# 5V-buck.net
KiCad netlist of a schematic drawn in Altium Designer
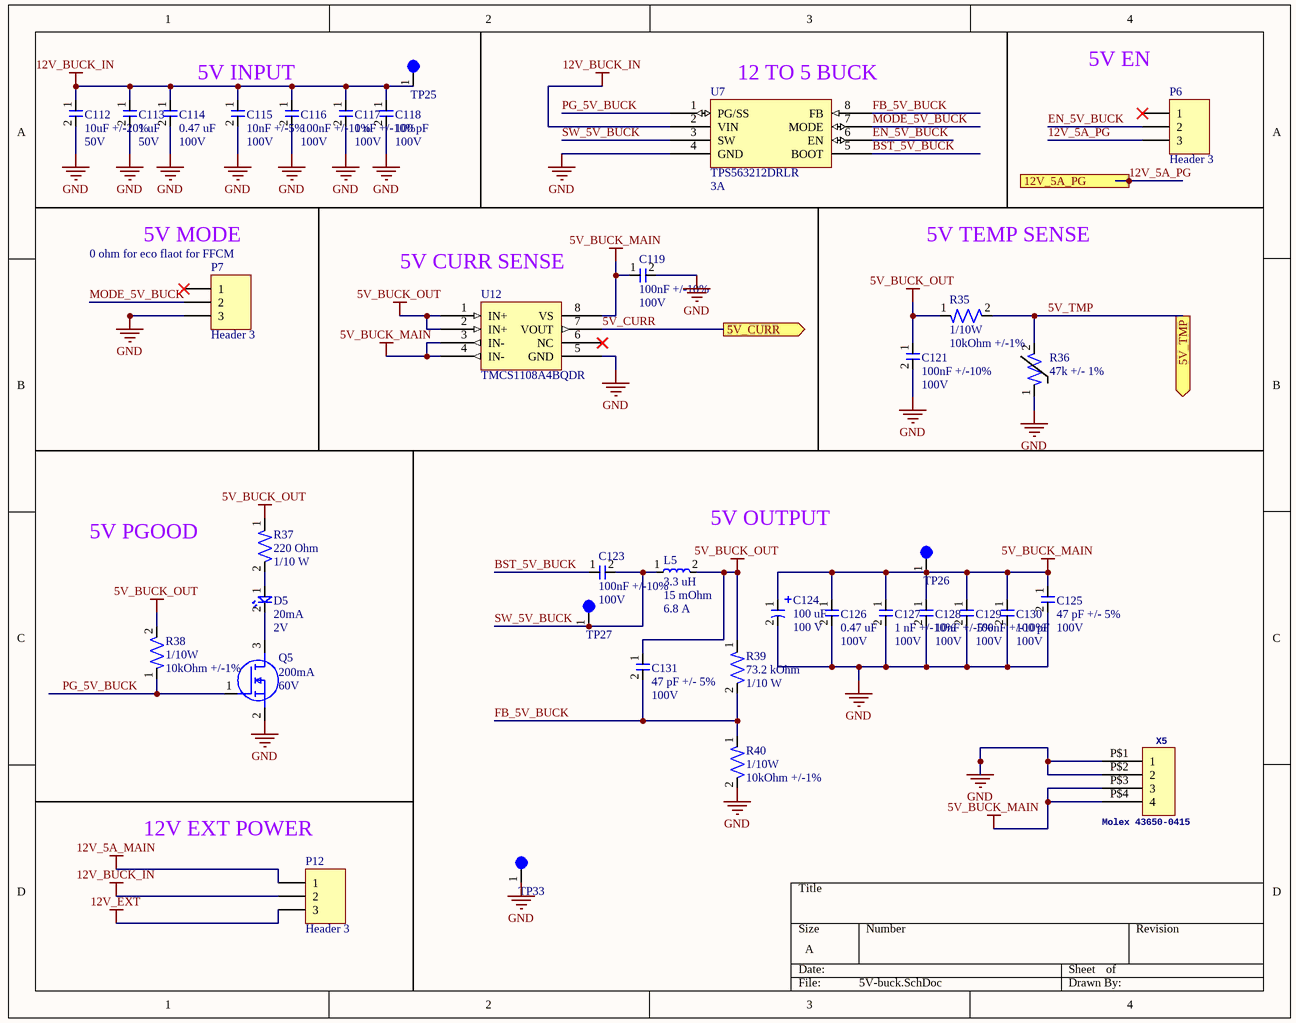
[diagram p0: 5V-buck.SchDoc]

(export (version "E")
  (design (tool "Eeschema 10.0.6"))
  (components
    (comp (ref "C112")
      (value "CL31B106KBHNNNE")
      (footprint "CAP-1206")
      (description "10 µF ±10% 50V Ceramic Capacitor X7R 1206 (3216 Metric)")
      (fields
        (field (name "MANUFACTURER") "Samsung Electro-Mechanics")
        (field (name "CAPACITANCE") "10uF +/-20%")
        (field (name "VOLTAGE RATING") "50V")
      )
      (libsource (lib "MasterLib") (part "CAP-10U-0001"))
    )
    (comp (ref "C113")
      (value "UMK107AB7105KA-T")
      (footprint "CAP-0603")
      (description "1 µF ±10% 50V Ceramic Capacitor X7R 0603 (1608 Metric)")
      (fields (field (name "CAPACITANCE") "1 uF") (field (name "VOLTAGE") "50V"))
      (libsource (lib "MasterLib") (part "CAP-1U-0002"))
    )
    (comp (ref "C114")
      (value "KAM21KR72A474KL")
      (footprint "CAP-0805")
      (description "0.47 µF ±10% 100V Ceramic Capacitor X7R 0805 (2012 Metric)")
      (fields
        (field (name "TOLERANCE") "+/- 10%")
        (field (name "CAPACITANCE") "0.47 uF")
        (field (name "VOLTAGE") "100V")
      )
      (libsource (lib "MasterLib") (part "CAP-0.47U-0001"))
    )
    (comp (ref "C115")
      (value "C1608C0G2A103J080AC")
      (footprint "CAP-0603")
      (description "CAP CER 10000PF 100V C0G 0603")
      (fields
        (field (name "MANUFACTURER") "TDK Corporation")
        (field (name "CAPACITANCE") "10nF +/-5%")
        (field (name "VOLTAGE RATING") "100V")
      )
      (libsource (lib "MasterLib") (part "CAP-10N-0002"))
    )
    (comp (ref "C116")
      (value "CC0603KRX7R0BB104")
      (footprint "CAP-0603")
      (description "CAP CER 0.1UF 100V X7R 0603")
      (fields
        (field (name "MANUFACTURER") "YAGEO")
        (field (name "CAPACITANCE") "100nF +/-10%")
        (field (name "VOLTAGE RATING") "100V")
      )
      (libsource (lib "MasterLib") (part "CAP-100N-0001"))
    )
    (comp (ref "C117")
      (value "C0603Y102K1RAC7867")
      (footprint "CAP-0603")
      (description "1000 pF ±10% 100V Ceramic Capacitor X7R 0603 (1608 Metric)")
      (fields (field (name "CAPACITANCE") "1 nF +/-10%") (field (name "VOLTAGE") "100V"))
      (libsource (lib "MasterLib") (part "CAP-1N-0001"))
    )
    (comp (ref "C118")
      (value "0603N101J101CT")
      (footprint "CAP-0603")
      (description "100 pF ±5% 100V Ceramic Capacitor C0G, NP0 0603 (1608 Metric)")
      (fields
        (field (name "TOLERANCE") "+/-5%")
        (field (name "CAPACITANCE") "100 pF")
        (field (name "VOLTAGE") "100V")
      )
      (libsource (lib "MasterLib") (part "CAP-100P-0002"))
    )
    (comp (ref "C119")
      (value "CC0603KRX7R0BB104")
      (footprint "CAP-0603")
      (description "CAP CER 0.1UF 100V X7R 0603")
      (fields
        (field (name "MANUFACTURER") "YAGEO")
        (field (name "CAPACITANCE") "100nF +/-10%")
        (field (name "VOLTAGE RATING") "100V")
      )
      (libsource (lib "MasterLib") (part "CAP-100N-0001"))
    )
    (comp (ref "C121")
      (value "CC0603KRX7R0BB104")
      (footprint "CAP-0603")
      (description "CAP CER 0.1UF 100V X7R 0603")
      (fields
        (field (name "MANUFACTURER") "YAGEO")
        (field (name "CAPACITANCE") "100nF +/-10%")
        (field (name "VOLTAGE RATING") "100V")
      )
      (libsource (lib "MasterLib") (part "CAP-100N-0001"))
    )
    (comp (ref "C123")
      (value "CC0603KRX7R0BB104")
      (footprint "CAP-0603")
      (description "CAP CER 0.1UF 100V X7R 0603")
      (fields
        (field (name "MANUFACTURER") "YAGEO")
        (field (name "CAPACITANCE") "100nF +/-10%")
        (field (name "VOLTAGE RATING") "100V")
      )
      (libsource (lib "MasterLib") (part "CAP-100N-0001"))
    )
    (comp (ref "C124")
      (value "100SEV100M12.5X16")
      (footprint "ELEC-100U-0001")
      (description "100 µF 100 V Aluminum Electrolytic Capacitors Radial, Can - SMD 2000 Hrs @ 85°C")
      (fields
        (field (name "MANUFACTURER") "Rubycon")
        (field (name "TOLERANCE") "+/- 20%")
        (field (name "CAPACITANCE") "100 uF")
        (field (name "VOLTAGE") "100 V")
      )
      (libsource (lib "MasterLib") (part "ELEC-100U-0001"))
    )
    (comp (ref "C125")
      (value "7447798111")
      (footprint "CAP-0603")
      (description "47 pF ±5% 100V Ceramic Capacitor C0G, NP0 0603 (1608 Metric)")
      (fields (field (name "CAPACITANCE") "47 pF +/- 5%") (field (name "VOLTAGE RATING") "100V"))
      (libsource (lib "MasterLib") (part "CAP-47P-0001"))
    )
    (comp (ref "C126")
      (value "KAM21KR72A474KL")
      (footprint "CAP-0805")
      (description "0.47 µF ±10% 100V Ceramic Capacitor X7R 0805 (2012 Metric)")
      (fields
        (field (name "TOLERANCE") "+/- 10%")
        (field (name "CAPACITANCE") "0.47 uF")
        (field (name "VOLTAGE") "100V")
      )
      (libsource (lib "MasterLib") (part "CAP-0.47U-0001"))
    )
    (comp (ref "C127")
      (value "C0603Y102K1RAC7867")
      (footprint "CAP-0603")
      (description "1000 pF ±10% 100V Ceramic Capacitor X7R 0603 (1608 Metric)")
      (fields (field (name "CAPACITANCE") "1 nF +/-10%") (field (name "VOLTAGE") "100V"))
      (libsource (lib "MasterLib") (part "CAP-1N-0001"))
    )
    (comp (ref "C128")
      (value "C1608C0G2A103J080AC")
      (footprint "CAP-0603")
      (description "CAP CER 10000PF 100V C0G 0603")
      (fields
        (field (name "MANUFACTURER") "TDK Corporation")
        (field (name "CAPACITANCE") "10nF +/-5%")
        (field (name "VOLTAGE RATING") "100V")
      )
      (libsource (lib "MasterLib") (part "CAP-10N-0002"))
    )
    (comp (ref "C129")
      (value "CC0603KRX7R0BB104")
      (footprint "CAP-0603")
      (description "CAP CER 0.1UF 100V X7R 0603")
      (fields
        (field (name "MANUFACTURER") "YAGEO")
        (field (name "CAPACITANCE") "100nF +/-10%")
        (field (name "VOLTAGE RATING") "100V")
      )
      (libsource (lib "MasterLib") (part "CAP-100N-0001"))
    )
    (comp (ref "C130")
      (value "0603N101J101CT")
      (footprint "CAP-0603")
      (description "100 pF ±5% 100V Ceramic Capacitor C0G, NP0 0603 (1608 Metric)")
      (fields
        (field (name "TOLERANCE") "+/-5%")
        (field (name "CAPACITANCE") "100 pF")
        (field (name "VOLTAGE") "100V")
      )
      (libsource (lib "MasterLib") (part "CAP-100P-0002"))
    )
    (comp (ref "C131")
      (value "7447798111")
      (footprint "CAP-0603")
      (description "47 pF ±5% 100V Ceramic Capacitor C0G, NP0 0603 (1608 Metric)")
      (fields (field (name "CAPACITANCE") "47 pF +/- 5%") (field (name "VOLTAGE RATING") "100V"))
      (libsource (lib "MasterLib") (part "CAP-47P-0001"))
    )
    (comp (ref "D5")
      (value "150060AS75000")
      (footprint "LED-0603")
      (description "CAP CER 0.1UF 100V X7R 0603")
      (fields
        (field (name "MANUFACTURER") "Wurth Electronik")
        (field (name "CURRENT RATING") "20mA")
        (field (name "VF") "2V")
      )
      (libsource (lib "MasterLib") (part "LED_Amber_0001"))
    )
    (comp (ref "L5")
      (value "SRR1240-3R3Y")
      (footprint "PWRIND-3.3U-0003")
      (description "3.3 µH Shielded Drum Core, Wirewound Inductor 6.8 A 15mOhm Max Nonstandard")
      (fields
        (field (name "TOLERANCE") "30%")
        (field (name "INDUCTANCE") "3.3 uH")
        (field (name "DCR") "15 mOhm")
        (field (name "DCI") "6.8 A")
      )
      (libsource (lib "MasterLib") (part "PWRIND-3.3U-0003"))
    )
    (comp (ref "P6")
      (value "Header 3")
      (footprint "HDR1X3")
      (description "Header, 3-Pin")
      (fields (field (name "PUBLISHER") "Altium Limited"))
      (libsource (lib "Miscellaneous Connectors") (part "Header 3"))
    )
    (comp (ref "P7")
      (value "Header 3")
      (footprint "HDR1X3")
      (description "Header, 3-Pin")
      (fields (field (name "PUBLISHER") "Altium Limited"))
      (libsource (lib "Miscellaneous Connectors") (part "Header 3"))
    )
    (comp (ref "P12")
      (value "Header 3")
      (footprint "HDR1X3")
      (description "Header, 3-Pin")
      (fields (field (name "PUBLISHER") "Altium Limited"))
      (libsource (lib "Miscellaneous Connectors") (part "Header 3"))
    )
    (comp (ref "Q5")
      (value "T2N7002AK,LM")
      (footprint "NMOS-SOT23-3")
      (description "MOSFET N-CH 60V 200MA SOT23")
      (fields
        (field (name "MANUFACTURER") "Toshiba")
        (field (name "ID-CONTINUOUS") "200mA")
        (field (name "VDS-MAX") "60V")
      )
      (libsource (lib "MasterLib") (part "NMOS-200MA-0001"))
    )
    (comp (ref "R35")
      (value "RC0603FR-0710KP")
      (footprint "RES-0603")
      (description "RES SMD 10K OHM 1% 1/10W 0603")
      (fields
        (field (name "MANUFACTURER") "YAGEO")
        (field (name "POWER RATING") "1/10W")
        (field (name "RESISTANCE") "10kOhm +/-1%")
      )
      (libsource (lib "MasterLib") (part "RES-10K-0002"))
    )
    (comp (ref "R36")
      (value "TMP6431DECR")
      (footprint "RES-0402")
      (description "PTC Thermistor 47 kOhms 0402 (1006 Metric)")
      (fields (field (name "MANUFACTURER") "Texas Instruments") (field (name "RESISTANCE") "47k +/- 1%"))
      (libsource (lib "MasterLib") (part "THERM-47K-0001"))
    )
    (comp (ref "R37")
      (value "CRGCQ0603J220R")
      (footprint "RES-0603")
      (fields
        (field (name "TOLERANCE") "+/- 5%")
        (field (name "RESISTANCE") "220 Ohm")
        (field (name "POWER") "1/10 W")
      )
      (libsource (lib "MasterLib") (part "RES-220-003"))
    )
    (comp (ref "R38")
      (value "RC0603FR-0710KP")
      (footprint "RES-0603")
      (description "RES SMD 10K OHM 1% 1/10W 0603")
      (fields
        (field (name "MANUFACTURER") "YAGEO")
        (field (name "POWER RATING") "1/10W")
        (field (name "RESISTANCE") "10kOhm +/-1%")
      )
      (libsource (lib "MasterLib") (part "RES-10K-0002"))
    )
    (comp (ref "R39")
      (value "RC0603FR-0773K2L")
      (footprint "RES-0603")
      (description "73.2 kOhms ±1% 0.1W, 1/10W Chip Resistor 0603 (1608 Metric) Moisture Resistant Thick Film")
      (fields
        (field (name "TOLERANCE") "1%")
        (field (name "RESISTANCE") "73.2 kOhm")
        (field (name "POWER") "1/10 W")
      )
      (libsource (lib "MasterLib") (part "RES-73.2K-0001"))
    )
    (comp (ref "R40")
      (value "RC0603FR-0710KP")
      (footprint "RES-0603")
      (description "RES SMD 10K OHM 1% 1/10W 0603")
      (fields
        (field (name "MANUFACTURER") "YAGEO")
        (field (name "POWER RATING") "1/10W")
        (field (name "RESISTANCE") "10kOhm +/-1%")
      )
      (libsource (lib "MasterLib") (part "RES-10K-0002"))
    )
    (comp (ref "TP25")
      (value "5003")
      (footprint "TEST-POINT-0001")
      (description "Oranange PC Test Point, Miniature Phoisphor Bronze Silver Plating Through Hole Mounting Type")
      (libsource (lib "MasterLib") (part "TEST-POINT-0001"))
    )
    (comp (ref "TP26")
      (value "5003")
      (footprint "TEST-POINT-0001")
      (description "Oranange PC Test Point, Miniature Phoisphor Bronze Silver Plating Through Hole Mounting Type")
      (libsource (lib "MasterLib") (part "TEST-POINT-0001"))
    )
    (comp (ref "TP27")
      (value "5003")
      (footprint "TEST-POINT-0001")
      (description "Oranange PC Test Point, Miniature Phoisphor Bronze Silver Plating Through Hole Mounting Type")
      (libsource (lib "MasterLib") (part "TEST-POINT-0001"))
    )
    (comp (ref "TP33")
      (value "5003")
      (footprint "TEST-POINT-0001")
      (description "Oranange PC Test Point, Miniature Phoisphor Bronze Silver Plating Through Hole Mounting Type")
      (libsource (lib "MasterLib") (part "TEST-POINT-0001"))
    )
    (comp (ref "U7")
      (value "TPS563212DRLR")
      (footprint "IC-SOT583")
      (description "Buck Switching Regulator IC Positive Adjustable 0.6V 1 Output 3A SOT-583")
      (fields (field (name "MANUFACTURER") "Texaas Instruments") (field (name "CURRENT") "3A"))
      (libsource (lib "MasterLib") (part "IC-BUCK-0008"))
    )
    (comp (ref "U12")
      (value "TMCS1108A4BQDR")
      (footprint "IC-CURRENT-0001")
      (description "Current Sensor 1 Channel Hall Effect Bidirectional 8-SOIC (0.154\", 3.90mm Width)")
      (libsource (lib "MasterLib") (part "IC-CURRENT-0004"))
    )
    (comp (ref "X5")
      (value "Molex 43650-0415")
      (footprint "43650-0415")
      (libsource (lib "Molex Microfit") (part "Micro-Fit Molex 4 Pin Vertical"))
    )
  )
  (nets
    (net (code "1") (name "/5V_CURR") (class "Default")
      (node (ref "U12") (pin "7") (pinfunction "VOUT_7") (pintype "output"))
    )
    (net (code "2") (name "/5V_TMP") (class "Default")
      (node (ref "R35") (pin "2") (pinfunction "2_2") (pintype "passive"))
      (node (ref "R36") (pin "2") (pinfunction "2_2") (pintype "passive"))
    )
    (net (code "3") (name "/12V_5A_PG") (class "Default")
      (node (ref "P6") (pin "3") (pinfunction "3_3") (pintype "passive"))
    )
    (net (code "4") (name "/BST_5V_BUCK") (class "Default")
      (node (ref "C123") (pin "1") (pinfunction "1_1") (pintype "passive"))
      (node (ref "U7") (pin "5") (pinfunction "BOOT_5") (pintype "power_in"))
    )
    (net (code "5") (name "/EN_5V_BUCK") (class "Default")
      (node (ref "P6") (pin "2") (pinfunction "2_2") (pintype "passive"))
      (node (ref "U7") (pin "6") (pinfunction "EN_6") (pintype "bidirectional"))
    )
    (net (code "6") (name "/FB_5V_BUCK") (class "Default")
      (node (ref "C131") (pin "2") (pinfunction "2_2") (pintype "passive"))
      (node (ref "R39") (pin "2") (pinfunction "2_2") (pintype "passive"))
      (node (ref "R40") (pin "1") (pinfunction "1_1") (pintype "passive"))
      (node (ref "U7") (pin "8") (pinfunction "FB_8") (pintype "input"))
    )
    (net (code "7") (name "/MODE_5V_BUCK") (class "Default")
      (node (ref "P7") (pin "2") (pinfunction "2_2") (pintype "passive"))
      (node (ref "U7") (pin "7") (pinfunction "MODE_7") (pintype "bidirectional"))
    )
    (net (code "8") (name "/PG_5V_BUCK") (class "Default")
      (node (ref "Q5") (pin "1") (pinfunction "G_1") (pintype "passive"))
      (node (ref "R38") (pin "1") (pinfunction "1_1") (pintype "passive"))
      (node (ref "U7") (pin "1") (pinfunction "PG/SS_1") (pintype "bidirectional"))
    )
    (net (code "9") (name "/SW_5V_BUCK") (class "Default")
      (node (ref "C123") (pin "2") (pinfunction "2_2") (pintype "passive"))
      (node (ref "L5") (pin "1") (pinfunction "1_1") (pintype "passive"))
      (node (ref "TP27") (pin "1") (pinfunction "0_1") (pintype "passive"))
      (node (ref "U7") (pin "3") (pinfunction "SW_3") (pintype "power_in"))
    )
    (net (code "10") (name "5V_BUCK_MAIN") (class "Default")
      (node (ref "C119") (pin "1") (pinfunction "1_1") (pintype "passive"))
      (node (ref "C124") (pin "1") (pinfunction "1_1") (pintype "passive"))
      (node (ref "C125") (pin "1") (pinfunction "1_1") (pintype "passive"))
      (node (ref "C126") (pin "1") (pinfunction "1_1") (pintype "passive"))
      (node (ref "C127") (pin "1") (pinfunction "1_1") (pintype "passive"))
      (node (ref "C128") (pin "1") (pinfunction "1_1") (pintype "passive"))
      (node (ref "C129") (pin "1") (pinfunction "1_1") (pintype "passive"))
      (node (ref "C130") (pin "1") (pinfunction "1_1") (pintype "passive"))
      (node (ref "TP26") (pin "1") (pinfunction "0_1") (pintype "passive"))
      (node (ref "U12") (pin "3") (pinfunction "IN-_3") (pintype "output"))
      (node (ref "U12") (pin "4") (pinfunction "IN-_4") (pintype "output"))
      (node (ref "U12") (pin "8") (pinfunction "VS_8") (pintype "power_in"))
      (node (ref "X5") (pin "P$3") (pinfunction "3_P$3") (pintype "passive"))
      (node (ref "X5") (pin "P$4") (pinfunction "4_P$4") (pintype "passive"))
    )
    (net (code "11") (name "5V_BUCK_OUT") (class "Default")
      (node (ref "C121") (pin "1") (pinfunction "1_1") (pintype "passive"))
      (node (ref "C131") (pin "1") (pinfunction "1_1") (pintype "passive"))
      (node (ref "L5") (pin "2") (pinfunction "2_2") (pintype "passive"))
      (node (ref "R35") (pin "1") (pinfunction "1_1") (pintype "passive"))
      (node (ref "R37") (pin "1") (pinfunction "1_1") (pintype "passive"))
      (node (ref "R38") (pin "2") (pinfunction "2_2") (pintype "passive"))
      (node (ref "R39") (pin "1") (pinfunction "1_1") (pintype "passive"))
      (node (ref "U12") (pin "1") (pinfunction "IN+_1") (pintype "input"))
      (node (ref "U12") (pin "2") (pinfunction "IN+_2") (pintype "input"))
    )
    (net (code "12") (name "12V_5A_MAIN") (class "Default")
      (node (ref "P12") (pin "1") (pinfunction "1_1") (pintype "passive"))
    )
    (net (code "13") (name "12V_BUCK_IN") (class "Default")
      (node (ref "C112") (pin "1") (pinfunction "1_1") (pintype "passive"))
      (node (ref "C113") (pin "1") (pinfunction "1_1") (pintype "passive"))
      (node (ref "C114") (pin "1") (pinfunction "1_1") (pintype "passive"))
      (node (ref "C115") (pin "1") (pinfunction "1_1") (pintype "passive"))
      (node (ref "C116") (pin "1") (pinfunction "1_1") (pintype "passive"))
      (node (ref "C117") (pin "1") (pinfunction "1_1") (pintype "passive"))
      (node (ref "C118") (pin "1") (pinfunction "1_1") (pintype "passive"))
      (node (ref "P12") (pin "2") (pinfunction "2_2") (pintype "passive"))
      (node (ref "TP25") (pin "1") (pinfunction "0_1") (pintype "passive"))
      (node (ref "U7") (pin "2") (pinfunction "VIN_2") (pintype "power_in"))
    )
    (net (code "14") (name "12V_EXT") (class "Default")
      (node (ref "P12") (pin "3") (pinfunction "3_3") (pintype "passive"))
    )
    (net (code "15") (name "GND") (class "Default")
      (node (ref "C112") (pin "2") (pinfunction "2_2") (pintype "passive"))
      (node (ref "C113") (pin "2") (pinfunction "2_2") (pintype "passive"))
      (node (ref "C114") (pin "2") (pinfunction "2_2") (pintype "passive"))
      (node (ref "C115") (pin "2") (pinfunction "2_2") (pintype "passive"))
      (node (ref "C116") (pin "2") (pinfunction "2_2") (pintype "passive"))
      (node (ref "C117") (pin "2") (pinfunction "2_2") (pintype "passive"))
      (node (ref "C118") (pin "2") (pinfunction "2_2") (pintype "passive"))
      (node (ref "C119") (pin "2") (pinfunction "2_2") (pintype "passive"))
      (node (ref "C121") (pin "2") (pinfunction "2_2") (pintype "passive"))
      (node (ref "C124") (pin "2") (pinfunction "2_2") (pintype "passive"))
      (node (ref "C125") (pin "2") (pinfunction "2_2") (pintype "passive"))
      (node (ref "C126") (pin "2") (pinfunction "2_2") (pintype "passive"))
      (node (ref "C127") (pin "2") (pinfunction "2_2") (pintype "passive"))
      (node (ref "C128") (pin "2") (pinfunction "2_2") (pintype "passive"))
      (node (ref "C129") (pin "2") (pinfunction "2_2") (pintype "passive"))
      (node (ref "C130") (pin "2") (pinfunction "2_2") (pintype "passive"))
      (node (ref "P7") (pin "3") (pinfunction "3_3") (pintype "passive"))
      (node (ref "Q5") (pin "2") (pinfunction "S_2") (pintype "passive"))
      (node (ref "R36") (pin "1") (pinfunction "1_1") (pintype "passive"))
      (node (ref "R40") (pin "2") (pinfunction "2_2") (pintype "passive"))
      (node (ref "TP33") (pin "1") (pinfunction "0_1") (pintype "passive"))
      (node (ref "U12") (pin "5") (pinfunction "GND_5") (pintype "power_in"))
      (node (ref "U7") (pin "4") (pinfunction "GND_4") (pintype "power_in"))
      (node (ref "X5") (pin "P$1") (pinfunction "1_P$1") (pintype "passive"))
      (node (ref "X5") (pin "P$2") (pinfunction "2_P$2") (pintype "passive"))
    )
    (net (code "16") (name "Net-(D5-Pad1)") (class "Default")
      (node (ref "D5") (pin "1") (pinfunction "1_1") (pintype "passive"))
      (node (ref "R37") (pin "2") (pinfunction "2_2") (pintype "passive"))
    )
    (net (code "17") (name "Net-(Q5-D)") (class "Default")
      (node (ref "D5") (pin "2") (pinfunction "2_2") (pintype "passive"))
      (node (ref "Q5") (pin "3") (pinfunction "D_3") (pintype "passive"))
    )
    (net (code "18") (name "unconnected-(P6-Pad1)") (class "Default")
      (node (ref "P6") (pin "1") (pinfunction "1_1") (pintype "passive+no_connect"))
    )
    (net (code "19") (name "unconnected-(P7-Pad1)") (class "Default")
      (node (ref "P7") (pin "1") (pinfunction "1_1") (pintype "passive+no_connect"))
    )
    (net (code "20") (name "unconnected-(U12-NC-Pad6)") (class "Default")
      (node (ref "U12") (pin "6") (pinfunction "NC_6") (pintype "tri_state+no_connect"))
    )
  )
)
